# Sheet1_DIO.net
KiCad netlist of a schematic drawn in Altium Designer
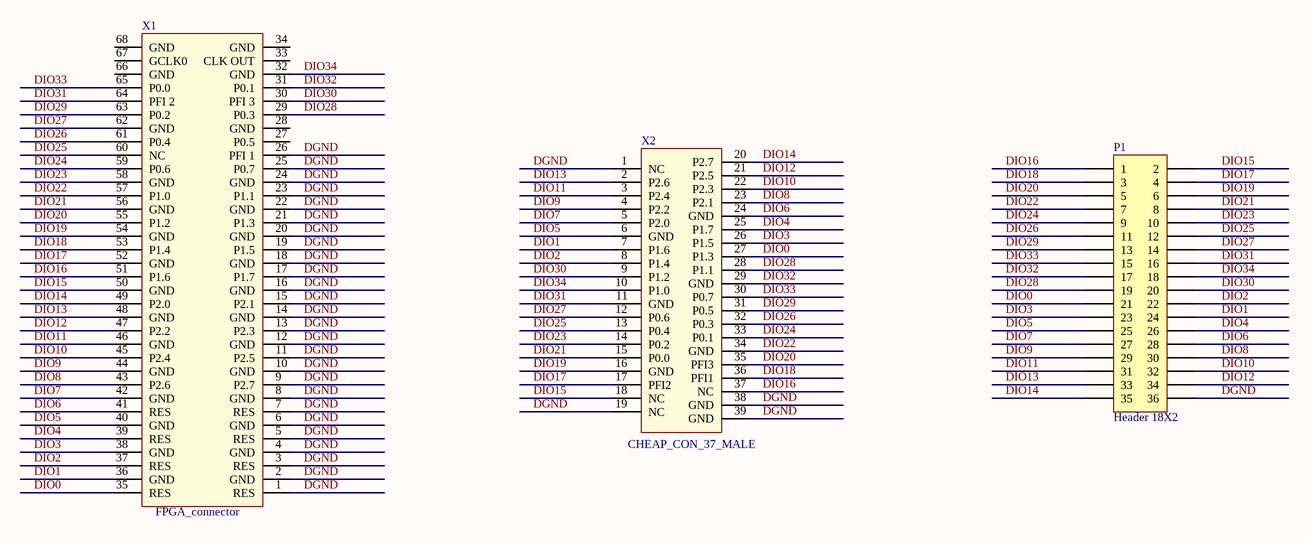
[diagram p0: Sheet1_DIO.SchDoc]

(export (version "E")
  (design (tool "Eeschema 10.0.6"))
  (components
    (comp (ref "P1")
      (value "Header 18X2")
      (footprint "HDR2X18")
      (description "Header, 18-Pin, Dual row")
      (fields (field (name "PUBLISHER") "Altium Limited"))
      (libsource (lib "Miscellaneous Connectors") (part "Header 18X2"))
    )
    (comp (ref "X1")
      (value "FPGA_connector")
      (footprint "FPGA")
      (libsource (lib "Schlib") (part "FPGA_Connector"))
    )
    (comp (ref "X2")
      (value "CHEAP_CON_37_MALE")
      (footprint "CHEAP_CONN_MALE")
      (libsource (lib "Schlib") (part "CHEAP_CON_37_MALE"))
    )
  )
  (nets
    (net (code "1") (name "/DGND") (class "Default")
      (node (ref "P1") (pin "36") (pinfunction "36_36") (pintype "passive"))
      (node (ref "X1") (pin "1") (pinfunction "RES_1") (pintype "passive"))
      (node (ref "X1") (pin "10") (pinfunction "GND_10") (pintype "passive"))
      (node (ref "X1") (pin "11") (pinfunction "P2.5_11") (pintype "passive"))
      (node (ref "X1") (pin "12") (pinfunction "GND_12") (pintype "passive"))
      (node (ref "X1") (pin "13") (pinfunction "P2.3_13") (pintype "passive"))
      (node (ref "X1") (pin "14") (pinfunction "GND_14") (pintype "passive"))
      (node (ref "X1") (pin "15") (pinfunction "P2.1_15") (pintype "passive"))
      (node (ref "X1") (pin "16") (pinfunction "GND_16") (pintype "passive"))
      (node (ref "X1") (pin "17") (pinfunction "P1.7_17") (pintype "passive"))
      (node (ref "X1") (pin "18") (pinfunction "GND_18") (pintype "passive"))
      (node (ref "X1") (pin "19") (pinfunction "P1.5_19") (pintype "passive"))
      (node (ref "X1") (pin "2") (pinfunction "GND_2") (pintype "passive"))
      (node (ref "X1") (pin "20") (pinfunction "GND_20") (pintype "passive"))
      (node (ref "X1") (pin "21") (pinfunction "P1.3_21") (pintype "passive"))
      (node (ref "X1") (pin "22") (pinfunction "GND_22") (pintype "passive"))
      (node (ref "X1") (pin "23") (pinfunction "P1.1_23") (pintype "passive"))
      (node (ref "X1") (pin "24") (pinfunction "GND_24") (pintype "passive"))
      (node (ref "X1") (pin "25") (pinfunction "P0.7_25") (pintype "passive"))
      (node (ref "X1") (pin "26") (pinfunction "PFI_1_26") (pintype "passive"))
      (node (ref "X1") (pin "3") (pinfunction "RES_3") (pintype "passive"))
      (node (ref "X1") (pin "4") (pinfunction "GND_4") (pintype "passive"))
      (node (ref "X1") (pin "5") (pinfunction "RES_5") (pintype "passive"))
      (node (ref "X1") (pin "6") (pinfunction "GND_6") (pintype "passive"))
      (node (ref "X1") (pin "7") (pinfunction "RES_7") (pintype "passive"))
      (node (ref "X1") (pin "8") (pinfunction "GND_8") (pintype "passive"))
      (node (ref "X1") (pin "9") (pinfunction "P2.7_9") (pintype "passive"))
      (node (ref "X2") (pin "1") (pinfunction "NC_1") (pintype "passive"))
      (node (ref "X2") (pin "19") (pinfunction "NC_19") (pintype "passive"))
      (node (ref "X2") (pin "38") (pinfunction "GND_38") (pintype "passive"))
      (node (ref "X2") (pin "39") (pinfunction "GND_39") (pintype "passive"))
    )
    (net (code "2") (name "/DIO0") (class "Default")
      (node (ref "P1") (pin "21") (pinfunction "21_21") (pintype "passive"))
      (node (ref "X1") (pin "35") (pinfunction "RES_35") (pintype "passive"))
      (node (ref "X2") (pin "27") (pinfunction "P1.3_27") (pintype "passive"))
    )
    (net (code "3") (name "/DIO1") (class "Default")
      (node (ref "P1") (pin "24") (pinfunction "24_24") (pintype "passive"))
      (node (ref "X1") (pin "36") (pinfunction "GND_36") (pintype "passive"))
      (node (ref "X2") (pin "7") (pinfunction "P1.6_7") (pintype "passive"))
    )
    (net (code "4") (name "/DIO2") (class "Default")
      (node (ref "P1") (pin "22") (pinfunction "22_22") (pintype "passive"))
      (node (ref "X1") (pin "37") (pinfunction "RES_37") (pintype "passive"))
      (node (ref "X2") (pin "8") (pinfunction "P1.4_8") (pintype "passive"))
    )
    (net (code "5") (name "/DIO3") (class "Default")
      (node (ref "P1") (pin "23") (pinfunction "23_23") (pintype "passive"))
      (node (ref "X1") (pin "38") (pinfunction "GND_38") (pintype "passive"))
      (node (ref "X2") (pin "26") (pinfunction "P1.5_26") (pintype "passive"))
    )
    (net (code "6") (name "/DIO4") (class "Default")
      (node (ref "P1") (pin "26") (pinfunction "26_26") (pintype "passive"))
      (node (ref "X1") (pin "39") (pinfunction "RES_39") (pintype "passive"))
      (node (ref "X2") (pin "25") (pinfunction "P1.7_25") (pintype "passive"))
    )
    (net (code "7") (name "/DIO5") (class "Default")
      (node (ref "P1") (pin "25") (pinfunction "25_25") (pintype "passive"))
      (node (ref "X1") (pin "40") (pinfunction "GND_40") (pintype "passive"))
      (node (ref "X2") (pin "6") (pinfunction "GND_6") (pintype "passive"))
    )
    (net (code "8") (name "/DIO6") (class "Default")
      (node (ref "P1") (pin "28") (pinfunction "28_28") (pintype "passive"))
      (node (ref "X1") (pin "41") (pinfunction "RES_41") (pintype "passive"))
      (node (ref "X2") (pin "24") (pinfunction "GND_24") (pintype "passive"))
    )
    (net (code "9") (name "/DIO7") (class "Default")
      (node (ref "P1") (pin "27") (pinfunction "27_27") (pintype "passive"))
      (node (ref "X1") (pin "42") (pinfunction "GND_42") (pintype "passive"))
      (node (ref "X2") (pin "5") (pinfunction "P2.0_5") (pintype "passive"))
    )
    (net (code "10") (name "/DIO8") (class "Default")
      (node (ref "P1") (pin "30") (pinfunction "30_30") (pintype "passive"))
      (node (ref "X1") (pin "43") (pinfunction "P2.6_43") (pintype "passive"))
      (node (ref "X2") (pin "23") (pinfunction "P2.1_23") (pintype "passive"))
    )
    (net (code "11") (name "/DIO9") (class "Default")
      (node (ref "P1") (pin "29") (pinfunction "29_29") (pintype "passive"))
      (node (ref "X1") (pin "44") (pinfunction "GND_44") (pintype "passive"))
      (node (ref "X2") (pin "4") (pinfunction "P2.2_4") (pintype "passive"))
    )
    (net (code "12") (name "/DIO10") (class "Default")
      (node (ref "P1") (pin "32") (pinfunction "32_32") (pintype "passive"))
      (node (ref "X1") (pin "45") (pinfunction "P2.4_45") (pintype "passive"))
      (node (ref "X2") (pin "22") (pinfunction "P2.3_22") (pintype "passive"))
    )
    (net (code "13") (name "/DIO11") (class "Default")
      (node (ref "P1") (pin "31") (pinfunction "31_31") (pintype "passive"))
      (node (ref "X1") (pin "46") (pinfunction "GND_46") (pintype "passive"))
      (node (ref "X2") (pin "3") (pinfunction "P2.4_3") (pintype "passive"))
    )
    (net (code "14") (name "/DIO12") (class "Default")
      (node (ref "P1") (pin "34") (pinfunction "34_34") (pintype "passive"))
      (node (ref "X1") (pin "47") (pinfunction "P2.2_47") (pintype "passive"))
      (node (ref "X2") (pin "21") (pinfunction "P2.5_21") (pintype "passive"))
    )
    (net (code "15") (name "/DIO13") (class "Default")
      (node (ref "P1") (pin "33") (pinfunction "33_33") (pintype "passive"))
      (node (ref "X1") (pin "48") (pinfunction "GND_48") (pintype "passive"))
      (node (ref "X2") (pin "2") (pinfunction "P2.6_2") (pintype "passive"))
    )
    (net (code "16") (name "/DIO14") (class "Default")
      (node (ref "P1") (pin "35") (pinfunction "35_35") (pintype "passive"))
      (node (ref "X1") (pin "49") (pinfunction "P2.0_49") (pintype "passive"))
      (node (ref "X2") (pin "20") (pinfunction "P2.7_20") (pintype "passive"))
    )
    (net (code "17") (name "/DIO15") (class "Default")
      (node (ref "P1") (pin "2") (pinfunction "2_2") (pintype "passive"))
      (node (ref "X1") (pin "50") (pinfunction "GND_50") (pintype "passive"))
      (node (ref "X2") (pin "18") (pinfunction "NC_18") (pintype "passive"))
    )
    (net (code "18") (name "/DIO16") (class "Default")
      (node (ref "P1") (pin "1") (pinfunction "1_1") (pintype "passive"))
      (node (ref "X1") (pin "51") (pinfunction "P1.6_51") (pintype "passive"))
      (node (ref "X2") (pin "37") (pinfunction "NC_37") (pintype "passive"))
    )
    (net (code "19") (name "/DIO17") (class "Default")
      (node (ref "P1") (pin "4") (pinfunction "4_4") (pintype "passive"))
      (node (ref "X1") (pin "52") (pinfunction "GND_52") (pintype "passive"))
      (node (ref "X2") (pin "17") (pinfunction "PFI2_17") (pintype "passive"))
    )
    (net (code "20") (name "/DIO18") (class "Default")
      (node (ref "P1") (pin "3") (pinfunction "3_3") (pintype "passive"))
      (node (ref "X1") (pin "53") (pinfunction "P1.4_53") (pintype "passive"))
      (node (ref "X2") (pin "36") (pinfunction "PFI1_36") (pintype "passive"))
    )
    (net (code "21") (name "/DIO19") (class "Default")
      (node (ref "P1") (pin "6") (pinfunction "6_6") (pintype "passive"))
      (node (ref "X1") (pin "54") (pinfunction "GND_54") (pintype "passive"))
      (node (ref "X2") (pin "16") (pinfunction "GND_16") (pintype "passive"))
    )
    (net (code "22") (name "/DIO20") (class "Default")
      (node (ref "P1") (pin "5") (pinfunction "5_5") (pintype "passive"))
      (node (ref "X1") (pin "55") (pinfunction "P1.2_55") (pintype "passive"))
      (node (ref "X2") (pin "35") (pinfunction "PFI3_35") (pintype "passive"))
    )
    (net (code "23") (name "/DIO21") (class "Default")
      (node (ref "P1") (pin "8") (pinfunction "8_8") (pintype "passive"))
      (node (ref "X1") (pin "56") (pinfunction "GND_56") (pintype "passive"))
      (node (ref "X2") (pin "15") (pinfunction "P0.0_15") (pintype "passive"))
    )
    (net (code "24") (name "/DIO22") (class "Default")
      (node (ref "P1") (pin "7") (pinfunction "7_7") (pintype "passive"))
      (node (ref "X1") (pin "57") (pinfunction "P1.0_57") (pintype "passive"))
      (node (ref "X2") (pin "34") (pinfunction "GND_34") (pintype "passive"))
    )
    (net (code "25") (name "/DIO23") (class "Default")
      (node (ref "P1") (pin "10") (pinfunction "10_10") (pintype "passive"))
      (node (ref "X1") (pin "58") (pinfunction "GND_58") (pintype "passive"))
      (node (ref "X2") (pin "14") (pinfunction "P0.2_14") (pintype "passive"))
    )
    (net (code "26") (name "/DIO24") (class "Default")
      (node (ref "P1") (pin "9") (pinfunction "9_9") (pintype "passive"))
      (node (ref "X1") (pin "59") (pinfunction "P0.6_59") (pintype "passive"))
      (node (ref "X2") (pin "33") (pinfunction "P0.1_33") (pintype "passive"))
    )
    (net (code "27") (name "/DIO25") (class "Default")
      (node (ref "P1") (pin "12") (pinfunction "12_12") (pintype "passive"))
      (node (ref "X1") (pin "60") (pinfunction "NC_60") (pintype "passive"))
      (node (ref "X2") (pin "13") (pinfunction "P0.4_13") (pintype "passive"))
    )
    (net (code "28") (name "/DIO26") (class "Default")
      (node (ref "P1") (pin "11") (pinfunction "11_11") (pintype "passive"))
      (node (ref "X1") (pin "61") (pinfunction "P0.4_61") (pintype "passive"))
      (node (ref "X2") (pin "32") (pinfunction "P0.3_32") (pintype "passive"))
    )
    (net (code "29") (name "/DIO27") (class "Default")
      (node (ref "P1") (pin "14") (pinfunction "14_14") (pintype "passive"))
      (node (ref "X1") (pin "62") (pinfunction "GND_62") (pintype "passive"))
      (node (ref "X2") (pin "12") (pinfunction "P0.6_12") (pintype "passive"))
    )
    (net (code "30") (name "/DIO28") (class "Default")
      (node (ref "P1") (pin "19") (pinfunction "19_19") (pintype "passive"))
      (node (ref "X1") (pin "29") (pinfunction "P0.3_29") (pintype "passive"))
      (node (ref "X2") (pin "28") (pinfunction "P1.1_28") (pintype "passive"))
    )
    (net (code "31") (name "/DIO29") (class "Default")
      (node (ref "P1") (pin "13") (pinfunction "13_13") (pintype "passive"))
      (node (ref "X1") (pin "63") (pinfunction "P0.2_63") (pintype "passive"))
      (node (ref "X2") (pin "31") (pinfunction "P0.5_31") (pintype "passive"))
    )
    (net (code "32") (name "/DIO30") (class "Default")
      (node (ref "P1") (pin "20") (pinfunction "20_20") (pintype "passive"))
      (node (ref "X1") (pin "30") (pinfunction "PFI_3_30") (pintype "passive"))
      (node (ref "X2") (pin "9") (pinfunction "P1.2_9") (pintype "passive"))
    )
    (net (code "33") (name "/DIO31") (class "Default")
      (node (ref "P1") (pin "16") (pinfunction "16_16") (pintype "passive"))
      (node (ref "X1") (pin "64") (pinfunction "PFI_2_64") (pintype "passive"))
      (node (ref "X2") (pin "11") (pinfunction "GND_11") (pintype "passive"))
    )
    (net (code "34") (name "/DIO32") (class "Default")
      (node (ref "P1") (pin "17") (pinfunction "17_17") (pintype "passive"))
      (node (ref "X1") (pin "31") (pinfunction "P0.1_31") (pintype "passive"))
      (node (ref "X2") (pin "29") (pinfunction "GND_29") (pintype "passive"))
    )
    (net (code "35") (name "/DIO33") (class "Default")
      (node (ref "P1") (pin "15") (pinfunction "15_15") (pintype "passive"))
      (node (ref "X1") (pin "65") (pinfunction "P0.0_65") (pintype "passive"))
      (node (ref "X2") (pin "30") (pinfunction "P0.7_30") (pintype "passive"))
    )
    (net (code "36") (name "/DIO34") (class "Default")
      (node (ref "P1") (pin "18") (pinfunction "18_18") (pintype "passive"))
      (node (ref "X1") (pin "32") (pinfunction "GND_32") (pintype "passive"))
      (node (ref "X2") (pin "10") (pinfunction "P1.0_10") (pintype "passive"))
    )
    (net (code "37") (name "unconnected-(X1-CLK_OUT-Pad33)") (class "Default")
      (node (ref "X1") (pin "33") (pinfunction "CLK_OUT_33") (pintype "passive"))
    )
    (net (code "38") (name "unconnected-(X1-GCLK0-Pad67)") (class "Default")
      (node (ref "X1") (pin "67") (pinfunction "GCLK0_67") (pintype "passive"))
    )
    (net (code "39") (name "unconnected-(X1-GND-Pad28)") (class "Default")
      (node (ref "X1") (pin "28") (pinfunction "GND_28") (pintype "passive"))
    )
    (net (code "40") (name "unconnected-(X1-GND-Pad34)") (class "Default")
      (node (ref "X1") (pin "34") (pinfunction "GND_34") (pintype "passive"))
    )
    (net (code "41") (name "unconnected-(X1-GND-Pad66)") (class "Default")
      (node (ref "X1") (pin "66") (pinfunction "GND_66") (pintype "passive"))
    )
    (net (code "42") (name "unconnected-(X1-GND-Pad68)") (class "Default")
      (node (ref "X1") (pin "68") (pinfunction "GND_68") (pintype "passive"))
    )
    (net (code "43") (name "unconnected-(X1-P0.5-Pad27)") (class "Default")
      (node (ref "X1") (pin "27") (pinfunction "P0.5_27") (pintype "passive"))
    )
  )
)
